# LDO.net
KiCad netlist of a schematic drawn in EAGLE
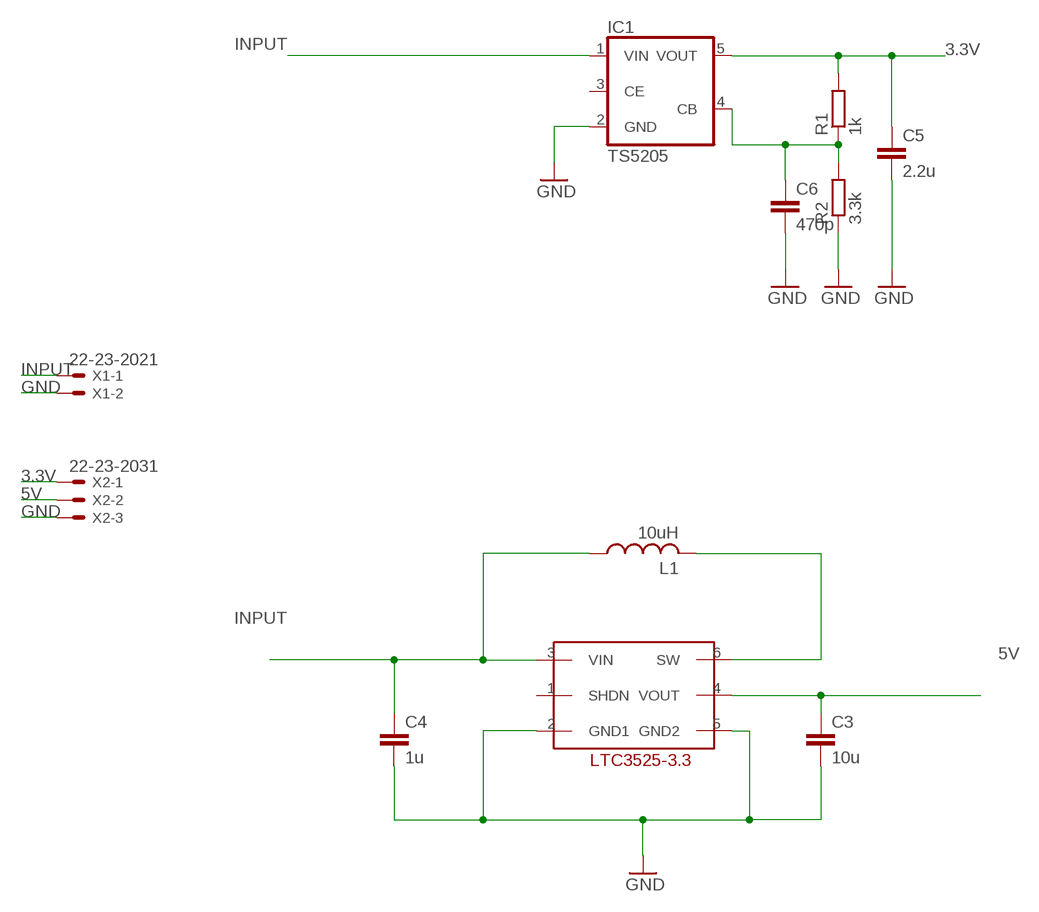
[diagram p0: schematic, sheet 1]

(export (version "E")
  (design (tool "Eeschema 10.0.6"))
  (components
    (comp (ref "C3")
      (value "10u")
      (footprint "eagle-import:C0805")
      (libsource (lib "eagle-import") (part "C-EUC0805"))
    )
    (comp (ref "C4")
      (value "1u")
      (footprint "eagle-import:C0805")
      (libsource (lib "eagle-import") (part "C-EUC0805"))
    )
    (comp (ref "C5")
      (value "2.2u")
      (footprint "eagle-import:C0805")
      (libsource (lib "eagle-import") (part "C-EUC0805"))
    )
    (comp (ref "C6")
      (value "470p")
      (footprint "eagle-import:C0805")
      (libsource (lib "eagle-import") (part "C-EUC0805"))
    )
    (comp (ref "IC1")
      (value "TS5205")
      (footprint "eagle-import:SOT25")
      (libsource (lib "eagle-import") (part "TS5205"))
    )
    (comp (ref "L1")
      (value "10uH")
      (footprint "eagle-import:L1812")
      (libsource (lib "eagle-import") (part "L-USL1812"))
    )
    (comp (ref "R1")
      (value "1k")
      (footprint "eagle-import:R0805")
      (libsource (lib "eagle-import") (part "R-EU_R0805"))
    )
    (comp (ref "R2")
      (value "3.3k")
      (footprint "eagle-import:R0805")
      (libsource (lib "eagle-import") (part "R-EU_R0805"))
    )
    (comp (ref "U$1")
      (value "LTC3525")
      (footprint "eagle-import:SC70-6")
      (libsource (lib "eagle-import") (part "LTC3525"))
    )
    (comp (ref "X1")
      (value "22-23-2021")
      (footprint "eagle-import:22-23-2021")
      (fields (field (name "MF") "MOLEX"))
      (libsource (lib "eagle-import") (part "22-23-2021"))
    )
    (comp (ref "X2")
      (value "22-23-2031")
      (footprint "eagle-import:22-23-2031")
      (fields (field (name "MF") "MOLEX"))
      (libsource (lib "eagle-import") (part "22-23-2031"))
    )
  )
  (nets
    (net (code "1") (name "/3.3V") (class "Default")
      (node (ref "C5") (pin "1") (pinfunction "1_1") (pintype "passive"))
      (node (ref "IC1") (pin "5") (pinfunction "VOUT_5") (pintype "passive"))
      (node (ref "R1") (pin "2") (pinfunction "2_2") (pintype "passive"))
      (node (ref "X2") (pin "1") (pinfunction "S_1") (pintype "passive"))
    )
    (net (code "2") (name "/5V") (class "Default")
      (node (ref "C3") (pin "1") (pinfunction "1_1") (pintype "passive"))
      (node (ref "U$1") (pin "4") (pinfunction "VOUT_4") (pintype "bidirectional"))
      (node (ref "X2") (pin "2") (pinfunction "S_2") (pintype "passive"))
    )
    (net (code "3") (name "/INPUT") (class "Default")
      (node (ref "C4") (pin "1") (pinfunction "1_1") (pintype "passive"))
      (node (ref "IC1") (pin "1") (pinfunction "VIN_1") (pintype "input"))
      (node (ref "L1") (pin "1") (pinfunction "1_1") (pintype "passive"))
      (node (ref "U$1") (pin "3") (pinfunction "VIN_3") (pintype "bidirectional"))
      (node (ref "X1") (pin "1") (pinfunction "S_1") (pintype "passive"))
    )
    (net (code "4") (name "GND") (class "Default")
      (node (ref "C3") (pin "2") (pinfunction "2_2") (pintype "passive"))
      (node (ref "C4") (pin "2") (pinfunction "2_2") (pintype "passive"))
      (node (ref "C5") (pin "2") (pinfunction "2_2") (pintype "passive"))
      (node (ref "C6") (pin "2") (pinfunction "2_2") (pintype "passive"))
      (node (ref "IC1") (pin "2") (pinfunction "GND_2") (pintype "passive"))
      (node (ref "R2") (pin "1") (pinfunction "1_1") (pintype "passive"))
      (node (ref "U$1") (pin "2") (pinfunction "GND1_2") (pintype "bidirectional"))
      (node (ref "U$1") (pin "5") (pinfunction "GND2_5") (pintype "bidirectional"))
      (node (ref "X1") (pin "2") (pinfunction "S_2") (pintype "passive"))
      (node (ref "X2") (pin "3") (pinfunction "S_3") (pintype "passive"))
    )
    (net (code "5") (name "Net-(IC1-CB)") (class "Default")
      (node (ref "C6") (pin "1") (pinfunction "1_1") (pintype "passive"))
      (node (ref "IC1") (pin "4") (pinfunction "CB_4") (pintype "input"))
      (node (ref "R1") (pin "1") (pinfunction "1_1") (pintype "passive"))
      (node (ref "R2") (pin "2") (pinfunction "2_2") (pintype "passive"))
    )
    (net (code "6") (name "Net-(U$1-SW)") (class "Default")
      (node (ref "L1") (pin "2") (pinfunction "2_2") (pintype "passive"))
      (node (ref "U$1") (pin "6") (pinfunction "SW_6") (pintype "bidirectional"))
    )
    (net (code "7") (name "unconnected-(IC1-CE-Pad3)") (class "Default")
      (node (ref "IC1") (pin "3") (pinfunction "CE_3") (pintype "input"))
    )
    (net (code "8") (name "unconnected-(U$1-SHDN-Pad1)") (class "Default")
      (node (ref "U$1") (pin "1") (pinfunction "SHDN_1") (pintype "bidirectional"))
    )
  )
)
